# Display.net
KiCad netlist of a schematic drawn in EAGLE
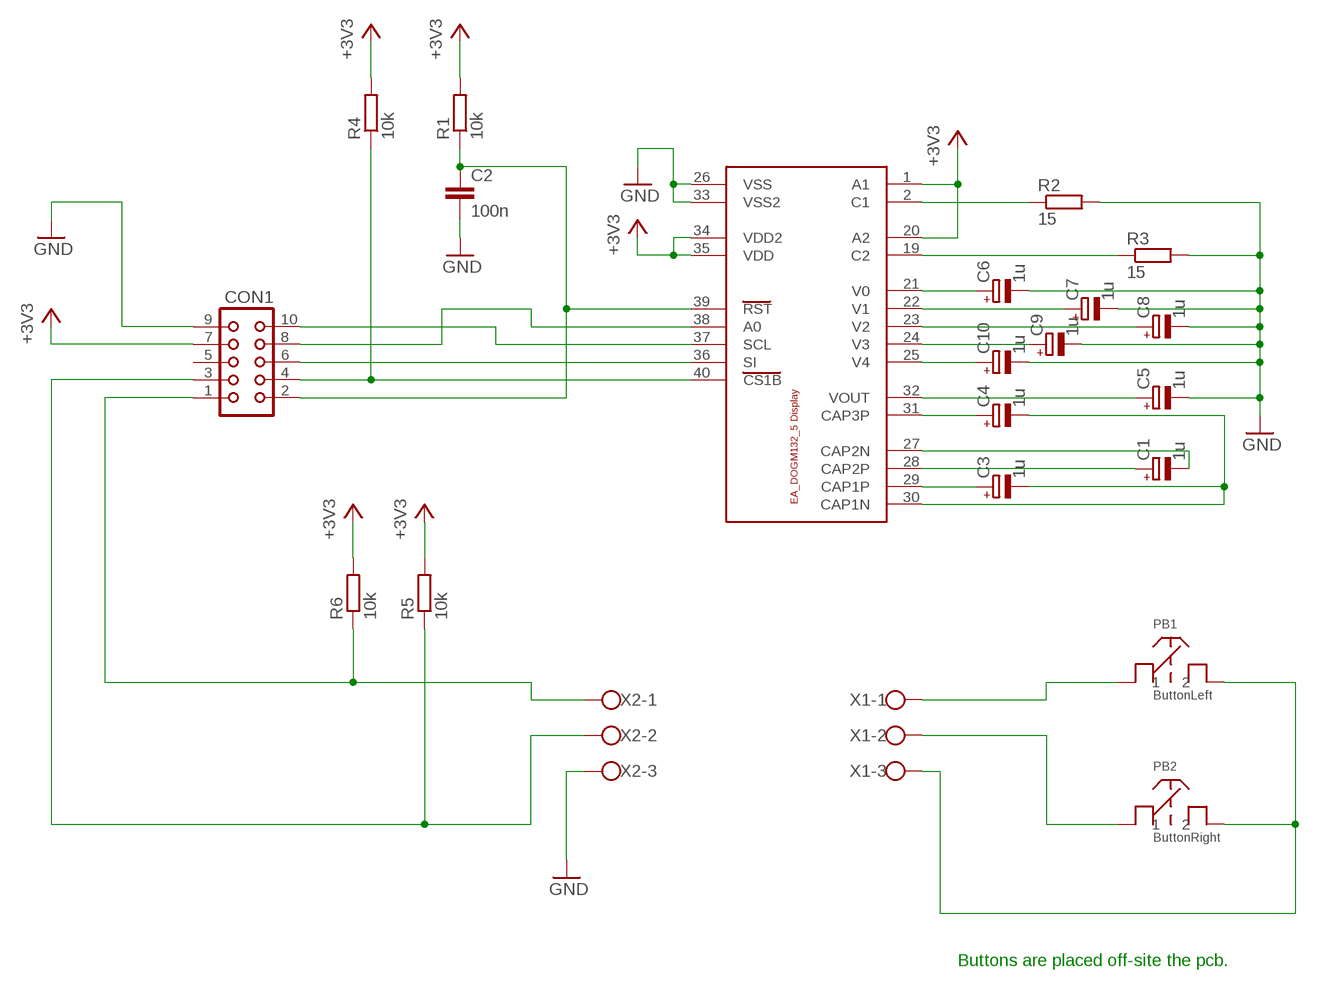
[diagram p0: schematic, sheet 1]

(export (version "E")
  (design (tool "Eeschema 10.0.6"))
  (components
    (comp (ref "C1")
      (value "1u")
      (footprint "eagle-import:PANASONIC_A")
      (libsource (lib "eagle-import") (part "CPOL-EUA"))
    )
    (comp (ref "C2")
      (value "100n")
      (footprint "eagle-import:C025-040X050")
      (libsource (lib "eagle-import") (part "C-EU025-040X050"))
    )
    (comp (ref "C3")
      (value "1u")
      (footprint "eagle-import:PANASONIC_A")
      (libsource (lib "eagle-import") (part "CPOL-EUA"))
    )
    (comp (ref "C4")
      (value "1u")
      (footprint "eagle-import:PANASONIC_A")
      (libsource (lib "eagle-import") (part "CPOL-EUA"))
    )
    (comp (ref "C5")
      (value "1u")
      (footprint "eagle-import:PANASONIC_A")
      (libsource (lib "eagle-import") (part "CPOL-EUA"))
    )
    (comp (ref "C6")
      (value "1u")
      (footprint "eagle-import:PANASONIC_A")
      (libsource (lib "eagle-import") (part "CPOL-EUA"))
    )
    (comp (ref "C7")
      (value "1u")
      (footprint "eagle-import:PANASONIC_A")
      (libsource (lib "eagle-import") (part "CPOL-EUA"))
    )
    (comp (ref "C8")
      (value "1u")
      (footprint "eagle-import:PANASONIC_A")
      (libsource (lib "eagle-import") (part "CPOL-EUA"))
    )
    (comp (ref "C9")
      (value "1u")
      (footprint "eagle-import:PANASONIC_A")
      (libsource (lib "eagle-import") (part "CPOL-EUA"))
    )
    (comp (ref "C10")
      (value "1u")
      (footprint "eagle-import:PANASONIC_A")
      (libsource (lib "eagle-import") (part "CPOL-EUA"))
    )
    (comp (ref "CON1")
      (value "CON10L")
      (footprint "eagle-import:CON10L")
      (libsource (lib "eagle-import") (part "CON10L"))
    )
    (comp (ref "PB1")
      (value "ButtonLeft")
      (footprint "eagle-import:PBNO-M")
      (libsource (lib "eagle-import") (part "PBNO-M"))
    )
    (comp (ref "PB2")
      (value "ButtonRight")
      (footprint "eagle-import:PBNO-M")
      (libsource (lib "eagle-import") (part "PBNO-M"))
    )
    (comp (ref "R1")
      (value "10k")
      (footprint "eagle-import:0204_5")
      (libsource (lib "eagle-import") (part "R-EU_0204/5"))
    )
    (comp (ref "R2")
      (value "15")
      (footprint "eagle-import:0204_5")
      (libsource (lib "eagle-import") (part "R-EU_0204/5"))
    )
    (comp (ref "R3")
      (value "15")
      (footprint "eagle-import:0204_5")
      (libsource (lib "eagle-import") (part "R-EU_0204/5"))
    )
    (comp (ref "R4")
      (value "10k")
      (footprint "eagle-import:0204_5")
      (libsource (lib "eagle-import") (part "R-EU_0204/5"))
    )
    (comp (ref "R5")
      (value "10k")
      (footprint "eagle-import:0204_5")
      (libsource (lib "eagle-import") (part "R-EU_0204/5"))
    )
    (comp (ref "R6")
      (value "10k")
      (footprint "eagle-import:0204_5")
      (libsource (lib "eagle-import") (part "R-EU_0204/5"))
    )
    (comp (ref "U$1")
      (value "EA_DOG-M_DISPLAY")
      (footprint "eagle-import:E_DOG-M_DISPLAY")
      (libsource (lib "eagle-import") (part "EA_DOG-M_DISPLAY"))
    )
    (comp (ref "X1")
      (value "W237-103")
      (footprint "eagle-import:W237-103")
      (fields (field (name "MPN") "237-103"))
      (libsource (lib "eagle-import") (part "W237-103"))
    )
    (comp (ref "X2")
      (value "W237-103")
      (footprint "eagle-import:W237-103")
      (fields (field (name "MPN") "237-103"))
      (libsource (lib "eagle-import") (part "W237-103"))
    )
  )
  (nets
    (net (code "1") (name "+3V3") (class "Default")
      (node (ref "CON1") (pin "7") (pinfunction "7_7") (pintype "passive"))
      (node (ref "R1") (pin "2") (pinfunction "2_2") (pintype "passive"))
      (node (ref "R4") (pin "2") (pinfunction "2_2") (pintype "passive"))
      (node (ref "R5") (pin "2") (pinfunction "2_2") (pintype "passive"))
      (node (ref "R6") (pin "2") (pinfunction "2_2") (pintype "passive"))
      (node (ref "U$1") (pin "1") (pinfunction "A1_1") (pintype "bidirectional"))
      (node (ref "U$1") (pin "20") (pinfunction "A2_20") (pintype "bidirectional"))
      (node (ref "U$1") (pin "34") (pinfunction "VDD2_34") (pintype "bidirectional"))
      (node (ref "U$1") (pin "35") (pinfunction "VDD_35") (pintype "bidirectional"))
    )
    (net (code "2") (name "GND") (class "Default")
      (node (ref "C10") (pin "-") (pinfunction "-_-") (pintype "passive"))
      (node (ref "C2") (pin "2") (pinfunction "2_2") (pintype "passive"))
      (node (ref "C5") (pin "-") (pinfunction "-_-") (pintype "passive"))
      (node (ref "C6") (pin "-") (pinfunction "-_-") (pintype "passive"))
      (node (ref "C7") (pin "-") (pinfunction "-_-") (pintype "passive"))
      (node (ref "C8") (pin "-") (pinfunction "-_-") (pintype "passive"))
      (node (ref "C9") (pin "-") (pinfunction "-_-") (pintype "passive"))
      (node (ref "CON1") (pin "9") (pinfunction "9_9") (pintype "passive"))
      (node (ref "R2") (pin "2") (pinfunction "2_2") (pintype "passive"))
      (node (ref "R3") (pin "2") (pinfunction "2_2") (pintype "passive"))
      (node (ref "U$1") (pin "26") (pinfunction "VSS_26") (pintype "bidirectional"))
      (node (ref "U$1") (pin "33") (pinfunction "VSS2_33") (pintype "bidirectional"))
      (node (ref "X2") (pin "3") (pinfunction "KL_3") (pintype "passive"))
    )
    (net (code "3") (name "Net-(PB1-1)") (class "Default")
      (node (ref "PB1") (pin "P$1") (pinfunction "1_P$1") (pintype "passive"))
      (node (ref "X1") (pin "1") (pinfunction "KL_1") (pintype "passive"))
    )
    (net (code "4") (name "Net-(PB1-2)") (class "Default")
      (node (ref "PB1") (pin "P$2") (pinfunction "2_P$2") (pintype "passive"))
      (node (ref "PB2") (pin "P$2") (pinfunction "2_P$2") (pintype "passive"))
      (node (ref "X1") (pin "3") (pinfunction "KL_3") (pintype "passive"))
    )
    (net (code "5") (name "Net-(PB2-1)") (class "Default")
      (node (ref "PB2") (pin "P$1") (pinfunction "1_P$1") (pintype "passive"))
      (node (ref "X1") (pin "2") (pinfunction "KL_2") (pintype "passive"))
    )
    (net (code "6") (name "Net-(U$1-A0)") (class "Default")
      (node (ref "CON1") (pin "8") (pinfunction "8_8") (pintype "passive"))
      (node (ref "U$1") (pin "38") (pinfunction "A0_38") (pintype "bidirectional"))
    )
    (net (code "7") (name "Net-(U$1-C1)") (class "Default")
      (node (ref "R2") (pin "1") (pinfunction "1_1") (pintype "passive"))
      (node (ref "U$1") (pin "2") (pinfunction "C1_2") (pintype "bidirectional"))
    )
    (net (code "8") (name "Net-(U$1-C2)") (class "Default")
      (node (ref "R3") (pin "1") (pinfunction "1_1") (pintype "passive"))
      (node (ref "U$1") (pin "19") (pinfunction "C2_19") (pintype "bidirectional"))
    )
    (net (code "9") (name "Net-(U$1-CAP1N)") (class "Default")
      (node (ref "C3") (pin "-") (pinfunction "-_-") (pintype "passive"))
      (node (ref "C4") (pin "-") (pinfunction "-_-") (pintype "passive"))
      (node (ref "U$1") (pin "30") (pinfunction "CAP1N_30") (pintype "bidirectional"))
    )
    (net (code "10") (name "Net-(U$1-CAP1P)") (class "Default")
      (node (ref "C3") (pin "+") (pinfunction "+_+") (pintype "passive"))
      (node (ref "U$1") (pin "29") (pinfunction "CAP1P_29") (pintype "bidirectional"))
    )
    (net (code "11") (name "Net-(U$1-CAP2N)") (class "Default")
      (node (ref "C1") (pin "-") (pinfunction "-_-") (pintype "passive"))
      (node (ref "U$1") (pin "27") (pinfunction "CAP2N_27") (pintype "bidirectional"))
    )
    (net (code "12") (name "Net-(U$1-CAP2P)") (class "Default")
      (node (ref "C1") (pin "+") (pinfunction "+_+") (pintype "passive"))
      (node (ref "U$1") (pin "28") (pinfunction "CAP2P_28") (pintype "bidirectional"))
    )
    (net (code "13") (name "Net-(U$1-CAP3P)") (class "Default")
      (node (ref "C4") (pin "+") (pinfunction "+_+") (pintype "passive"))
      (node (ref "U$1") (pin "31") (pinfunction "CAP3P_31") (pintype "bidirectional"))
    )
    (net (code "14") (name "Net-(U$1-CS1B)") (class "Default")
      (node (ref "CON1") (pin "4") (pinfunction "4_4") (pintype "passive"))
      (node (ref "R4") (pin "1") (pinfunction "1_1") (pintype "passive"))
      (node (ref "U$1") (pin "40") (pinfunction "CS1B_40") (pintype "bidirectional"))
    )
    (net (code "15") (name "Net-(U$1-RST)") (class "Default")
      (node (ref "C2") (pin "1") (pinfunction "1_1") (pintype "passive"))
      (node (ref "CON1") (pin "2") (pinfunction "2_2") (pintype "passive"))
      (node (ref "R1") (pin "1") (pinfunction "1_1") (pintype "passive"))
      (node (ref "U$1") (pin "39") (pinfunction "RST_39") (pintype "bidirectional"))
    )
    (net (code "16") (name "Net-(U$1-SCL)") (class "Default")
      (node (ref "CON1") (pin "10") (pinfunction "10_10") (pintype "passive"))
      (node (ref "U$1") (pin "37") (pinfunction "SCL_37") (pintype "bidirectional"))
    )
    (net (code "17") (name "Net-(U$1-SI)") (class "Default")
      (node (ref "CON1") (pin "6") (pinfunction "6_6") (pintype "passive"))
      (node (ref "U$1") (pin "36") (pinfunction "SI_36") (pintype "bidirectional"))
    )
    (net (code "18") (name "Net-(U$1-V0)") (class "Default")
      (node (ref "C6") (pin "+") (pinfunction "+_+") (pintype "passive"))
      (node (ref "U$1") (pin "21") (pinfunction "V0_21") (pintype "power_in"))
    )
    (net (code "19") (name "Net-(U$1-V1)") (class "Default")
      (node (ref "C7") (pin "+") (pinfunction "+_+") (pintype "passive"))
      (node (ref "U$1") (pin "22") (pinfunction "V1_22") (pintype "power_in"))
    )
    (net (code "20") (name "Net-(U$1-V2)") (class "Default")
      (node (ref "C8") (pin "+") (pinfunction "+_+") (pintype "passive"))
      (node (ref "U$1") (pin "23") (pinfunction "V2_23") (pintype "bidirectional"))
    )
    (net (code "21") (name "Net-(U$1-V3)") (class "Default")
      (node (ref "C9") (pin "+") (pinfunction "+_+") (pintype "passive"))
      (node (ref "U$1") (pin "24") (pinfunction "V3_24") (pintype "bidirectional"))
    )
    (net (code "22") (name "Net-(U$1-V4)") (class "Default")
      (node (ref "C10") (pin "+") (pinfunction "+_+") (pintype "passive"))
      (node (ref "U$1") (pin "25") (pinfunction "V4_25") (pintype "bidirectional"))
    )
    (net (code "23") (name "Net-(U$1-VOUT)") (class "Default")
      (node (ref "C5") (pin "+") (pinfunction "+_+") (pintype "passive"))
      (node (ref "U$1") (pin "32") (pinfunction "VOUT_32") (pintype "bidirectional"))
    )
    (net (code "24") (name "Net-(X2A-KL)") (class "Default")
      (node (ref "CON1") (pin "1") (pinfunction "1_1") (pintype "passive"))
      (node (ref "R6") (pin "1") (pinfunction "1_1") (pintype "passive"))
      (node (ref "X2") (pin "1") (pinfunction "KL_1") (pintype "passive"))
    )
    (net (code "25") (name "Net-(X2B-KL)") (class "Default")
      (node (ref "CON1") (pin "3") (pinfunction "3_3") (pintype "passive"))
      (node (ref "R5") (pin "1") (pinfunction "1_1") (pintype "passive"))
      (node (ref "X2") (pin "2") (pinfunction "KL_2") (pintype "passive"))
    )
    (net (code "26") (name "unconnected-(CON1-Pad5)") (class "Default")
      (node (ref "CON1") (pin "5") (pinfunction "5_5") (pintype "passive"))
    )
  )
)
